# moonclock.net
KiCad netlist of a schematic drawn in EAGLE
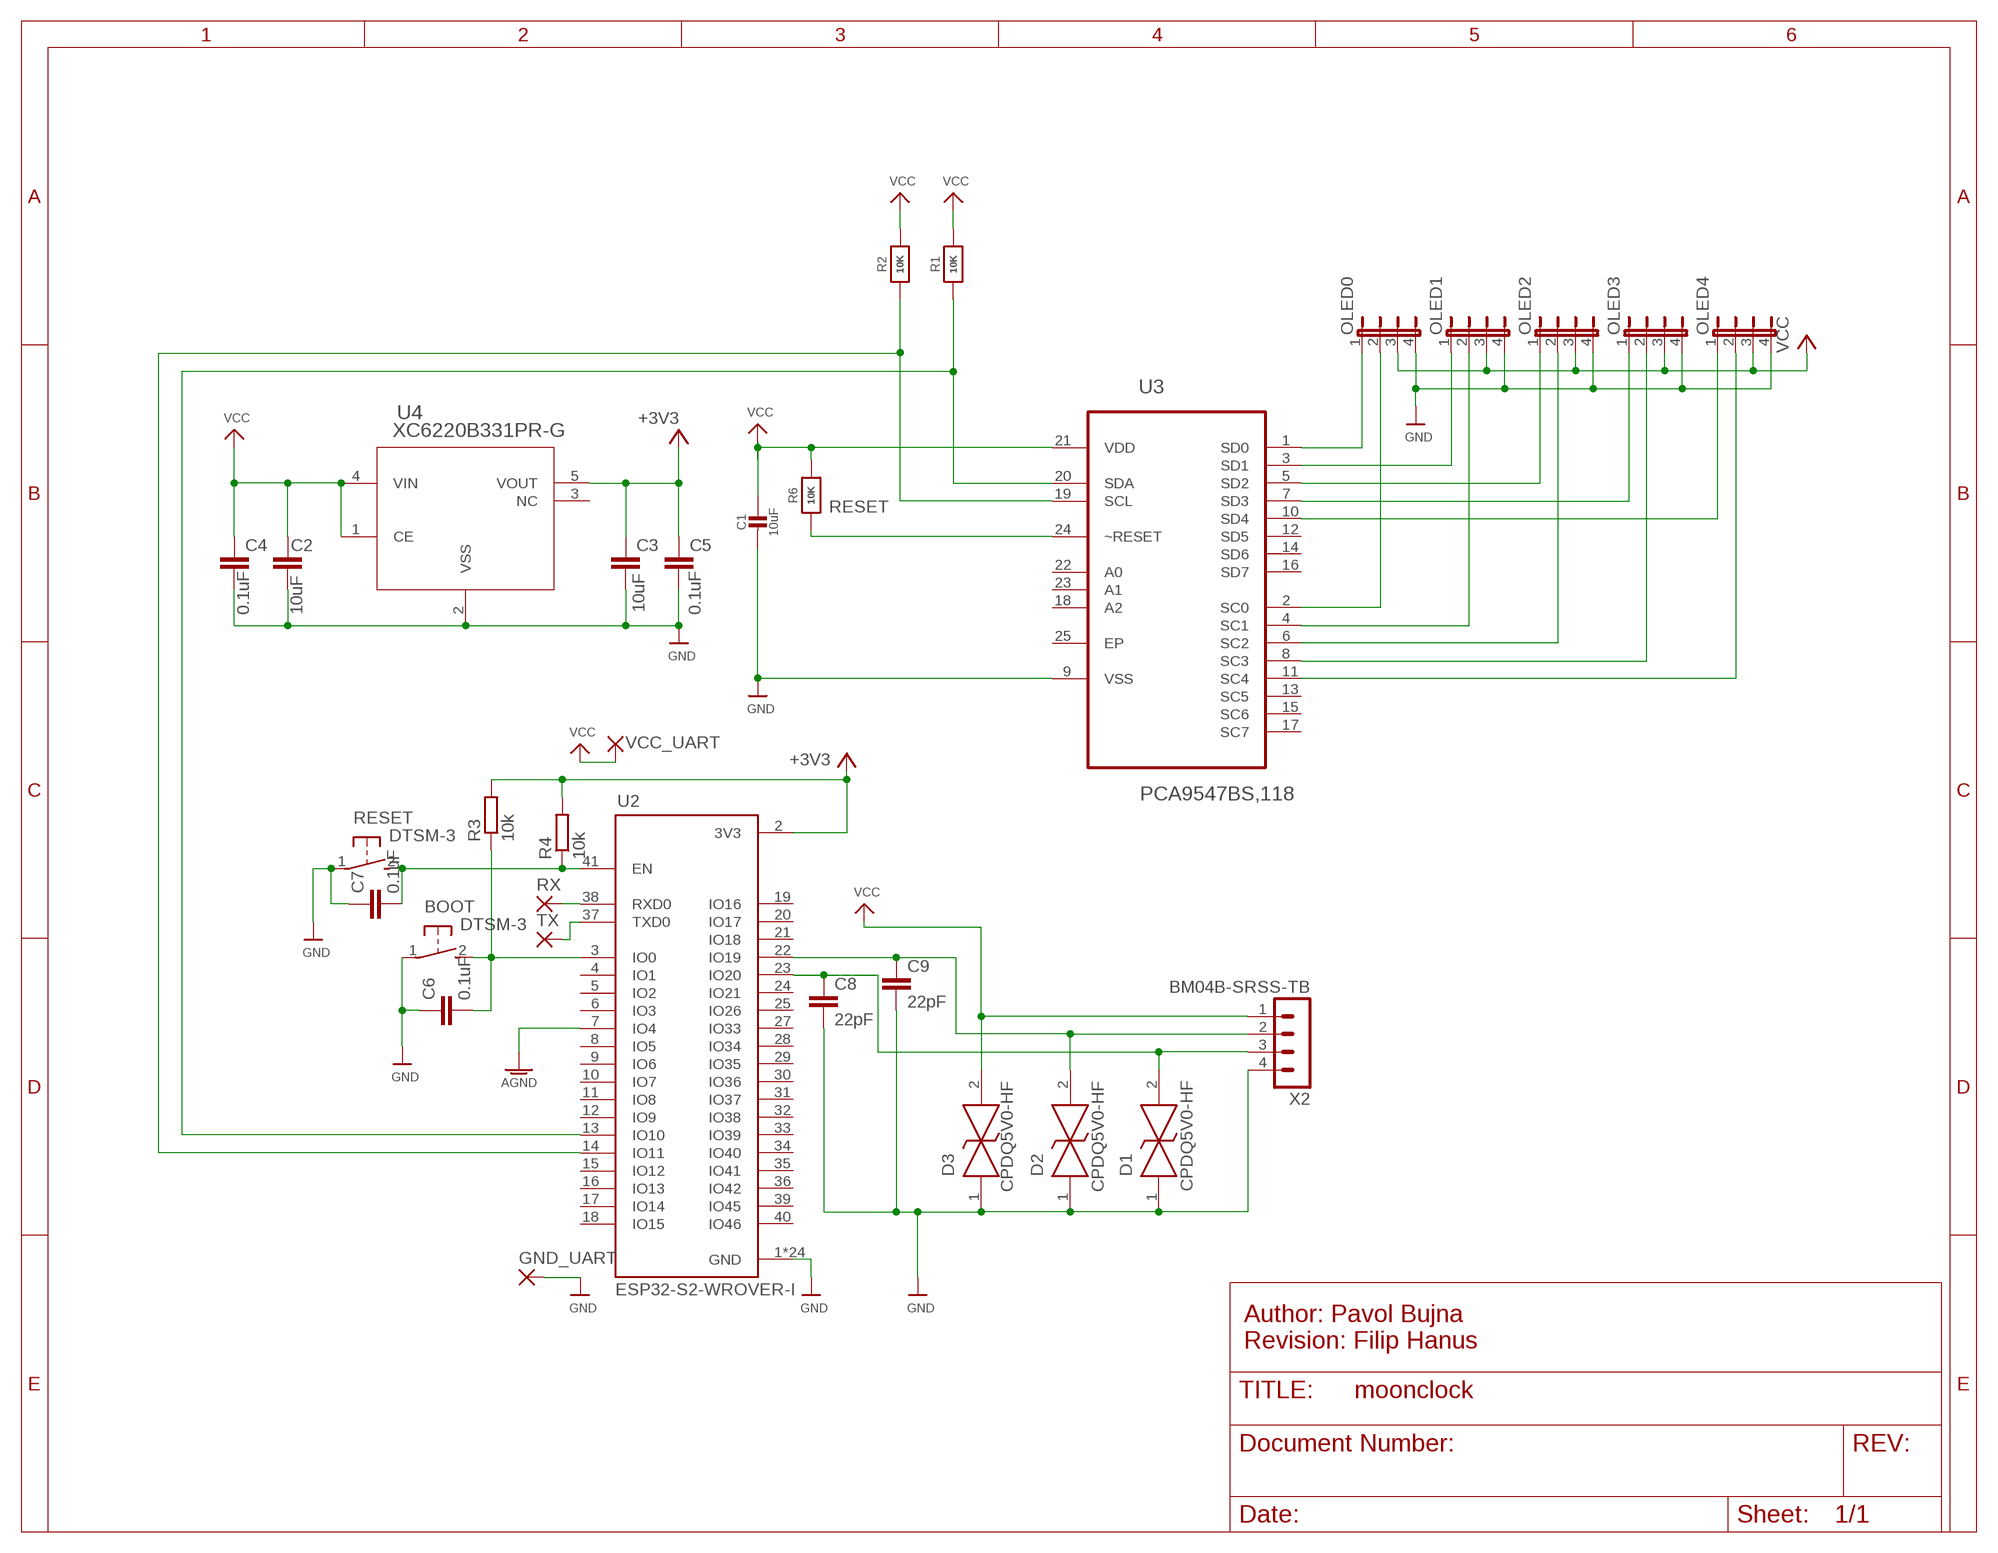
[diagram p0: schematic, sheet 1]

(export (version "E")
  (design (tool "Eeschema 10.0.6"))
  (components
    (comp (ref "BOOT")
      (value "DTSM-3")
      (footprint "eagle-import:DTSM-3")
      (libsource (lib "eagle-import") (part "DTSM-3"))
    )
    (comp (ref "C1")
      (value "10uF")
      (footprint "eagle-import:0805-NO")
      (libsource (lib "eagle-import") (part "CAP_CERAMIC0805-NOOUTLINE"))
    )
    (comp (ref "C2")
      (value "10uF")
      (footprint "eagle-import:C0805")
      (libsource (lib "eagle-import") (part "C-EUC0805"))
    )
    (comp (ref "C3")
      (value "10uF")
      (footprint "eagle-import:C0805")
      (libsource (lib "eagle-import") (part "C-EUC0805"))
    )
    (comp (ref "C4")
      (value "0.1uF")
      (footprint "eagle-import:C0805")
      (libsource (lib "eagle-import") (part "C-EUC0805"))
    )
    (comp (ref "C5")
      (value "0.1uF")
      (footprint "eagle-import:C0805")
      (libsource (lib "eagle-import") (part "C-EUC0805"))
    )
    (comp (ref "C6")
      (value "0.1uF")
      (footprint "eagle-import:C0805")
      (libsource (lib "eagle-import") (part "C-EUC0805"))
    )
    (comp (ref "C7")
      (value "0.1uF")
      (footprint "eagle-import:C0805")
      (libsource (lib "eagle-import") (part "C-EUC0805"))
    )
    (comp (ref "C8")
      (value "22pF")
      (footprint "eagle-import:C0805")
      (libsource (lib "eagle-import") (part "C-EUC0805"))
    )
    (comp (ref "C9")
      (value "22pF")
      (footprint "eagle-import:C0805")
      (libsource (lib "eagle-import") (part "C-EUC0805"))
    )
    (comp (ref "D1")
      (value "CPDQ5V0-HF")
      (footprint "eagle-import:MBTB-D-SOD-923F-IMP-0402")
      (fields (field (name "MF") "Comchip Technology"))
      (libsource (lib "eagle-import") (part "CPDQ5V0-HF"))
    )
    (comp (ref "D2")
      (value "CPDQ5V0-HF")
      (footprint "eagle-import:MBTB-D-SOD-923F-IMP-0402")
      (fields (field (name "MF") "Comchip Technology"))
      (libsource (lib "eagle-import") (part "CPDQ5V0-HF"))
    )
    (comp (ref "D3")
      (value "CPDQ5V0-HF")
      (footprint "eagle-import:MBTB-D-SOD-923F-IMP-0402")
      (fields (field (name "MF") "Comchip Technology"))
      (libsource (lib "eagle-import") (part "CPDQ5V0-HF"))
    )
    (comp (ref "GND_UART")
      (value "SMD2")
      (footprint "eagle-import:SMD1,27-2,54")
      (libsource (lib "eagle-import") (part "SMD2"))
    )
    (comp (ref "OLED0")
      (value "JP4E")
      (footprint "eagle-import:JP4")
      (libsource (lib "eagle-import") (part "JP4E"))
    )
    (comp (ref "OLED1")
      (value "JP4E")
      (footprint "eagle-import:JP4")
      (libsource (lib "eagle-import") (part "JP4E"))
    )
    (comp (ref "OLED2")
      (value "JP4E")
      (footprint "eagle-import:JP4")
      (libsource (lib "eagle-import") (part "JP4E"))
    )
    (comp (ref "OLED3")
      (value "JP4E")
      (footprint "eagle-import:JP4")
      (libsource (lib "eagle-import") (part "JP4E"))
    )
    (comp (ref "OLED4")
      (value "JP4E")
      (footprint "eagle-import:JP4")
      (libsource (lib "eagle-import") (part "JP4E"))
    )
    (comp (ref "R1")
      (value "10K")
      (footprint "eagle-import:0805-NO")
      (libsource (lib "eagle-import") (part "RESISTOR0805_NOOUTLINE"))
    )
    (comp (ref "R2")
      (value "10K")
      (footprint "eagle-import:0805-NO")
      (libsource (lib "eagle-import") (part "RESISTOR0805_NOOUTLINE"))
    )
    (comp (ref "R3")
      (value "10k")
      (footprint "eagle-import:R0805")
      (libsource (lib "eagle-import") (part "R-EU_R0805"))
    )
    (comp (ref "R4")
      (value "10k")
      (footprint "eagle-import:R0805")
      (libsource (lib "eagle-import") (part "R-EU_R0805"))
    )
    (comp (ref "R6")
      (value "10K")
      (footprint "eagle-import:_0805MP")
      (libsource (lib "eagle-import") (part "RESISTOR_0805MP"))
    )
    (comp (ref "RESET")
      (value "DTSM-3")
      (footprint "eagle-import:DTSM-3")
      (libsource (lib "eagle-import") (part "DTSM-3"))
    )
    (comp (ref "RX")
      (value "SMD2")
      (footprint "eagle-import:SMD1,27-2,54")
      (libsource (lib "eagle-import") (part "SMD2"))
    )
    (comp (ref "TX")
      (value "SMD2")
      (footprint "eagle-import:SMD1,27-2,54")
      (libsource (lib "eagle-import") (part "SMD2"))
    )
    (comp (ref "U2")
      (value "ESP32-S2-WROVER-I")
      (footprint "eagle-import:ESP32-S2-WROVER-I")
      (libsource (lib "eagle-import") (part "ESP32-S2-WROVER-I"))
    )
    (comp (ref "U3")
      (value "PCA9547BS,118")
      (footprint "eagle-import:QFN50P400X400X100-25N")
      (fields (field (name "MF") "NXP Semiconductors"))
      (libsource (lib "eagle-import") (part "PCA9547BS,118"))
    )
    (comp (ref "U4")
      (value "XC6220B331PR-G")
      (footprint "eagle-import:SOT-89-5_TOR")
      (fields (field (name "COPYRIGHT") "Copyright (C) 2022 Ultra Librarian. All rights reserved."))
      (libsource (lib "eagle-import") (part "XC6220B331PR-G"))
    )
    (comp (ref "VCC_UART")
      (value "SMD2")
      (footprint "eagle-import:SMD1,27-2,54")
      (libsource (lib "eagle-import") (part "SMD2"))
    )
    (comp (ref "X2")
      (value "BM04B-SRSS-TB")
      (footprint "eagle-import:BM04B-SRSS-TB")
      (libsource (lib "eagle-import") (part "BM04B-SRSS-TB"))
    )
  )
  (nets
    (net (code "1") (name "+3V3") (class "Default")
      (node (ref "C3") (pin "1") (pinfunction "1_1") (pintype "passive"))
      (node (ref "C5") (pin "1") (pinfunction "1_1") (pintype "passive"))
      (node (ref "R3") (pin "2") (pinfunction "2_2") (pintype "passive"))
      (node (ref "R4") (pin "2") (pinfunction "2_2") (pintype "passive"))
      (node (ref "U4") (pin "5") (pinfunction "VOUT_5") (pintype "output"))
    )
    (net (code "2") (name "/RESET") (class "Default")
      (node (ref "R6") (pin "1") (pinfunction "1_1") (pintype "passive"))
      (node (ref "U3") (pin "24") (pinfunction "~{RESET}_24") (pintype "input"))
    )
    (net (code "3") (name "AGND") (class "Default")
      (node (ref "U2") (pin "7") (pinfunction "IO4_7") (pintype "bidirectional"))
    )
    (net (code "4") (name "GND") (class "Default")
      (node (ref "BOOT") (pin "1") (pinfunction "1_1") (pintype "passive"))
      (node (ref "C1") (pin "2") (pinfunction "2_2") (pintype "passive"))
      (node (ref "C2") (pin "2") (pinfunction "2_2") (pintype "passive"))
      (node (ref "C3") (pin "2") (pinfunction "2_2") (pintype "passive"))
      (node (ref "C4") (pin "2") (pinfunction "2_2") (pintype "passive"))
      (node (ref "C5") (pin "2") (pinfunction "2_2") (pintype "passive"))
      (node (ref "C6") (pin "1") (pinfunction "1_1") (pintype "passive"))
      (node (ref "C7") (pin "1") (pinfunction "1_1") (pintype "passive"))
      (node (ref "C8") (pin "2") (pinfunction "2_2") (pintype "passive"))
      (node (ref "C9") (pin "2") (pinfunction "2_2") (pintype "passive"))
      (node (ref "D1") (pin "1") (pinfunction "K_1") (pintype "bidirectional"))
      (node (ref "D2") (pin "1") (pinfunction "K_1") (pintype "bidirectional"))
      (node (ref "D3") (pin "1") (pinfunction "K_1") (pintype "bidirectional"))
      (node (ref "GND_UART") (pin "1") (pinfunction "P_1") (pintype "passive"))
      (node (ref "OLED0") (pin "4") (pinfunction "4_4") (pintype "passive"))
      (node (ref "OLED1") (pin "4") (pinfunction "4_4") (pintype "passive"))
      (node (ref "OLED2") (pin "4") (pinfunction "4_4") (pintype "passive"))
      (node (ref "OLED3") (pin "4") (pinfunction "4_4") (pintype "passive"))
      (node (ref "OLED4") (pin "4") (pinfunction "4_4") (pintype "passive"))
      (node (ref "RESET") (pin "1") (pinfunction "1_1") (pintype "passive"))
      (node (ref "U2") (pin "1") (pinfunction "GND_1") (pintype "power_in"))
      (node (ref "U2") (pin "26") (pinfunction "GND_26") (pintype "power_in"))
      (node (ref "U2") (pin "42") (pinfunction "GND_42") (pintype "power_in"))
      (node (ref "U2") (pin "43.1") (pinfunction "GND_43.1") (pintype "power_in"))
      (node (ref "U2") (pin "43.10") (pinfunction "GND_43.10") (pintype "power_in"))
      (node (ref "U2") (pin "43.11") (pinfunction "GND_43.11") (pintype "power_in"))
      (node (ref "U2") (pin "43.12") (pinfunction "GND_43.12") (pintype "power_in"))
      (node (ref "U2") (pin "43.13") (pinfunction "GND_43.13") (pintype "power_in"))
      (node (ref "U2") (pin "43.14") (pinfunction "GND_43.14") (pintype "power_in"))
      (node (ref "U2") (pin "43.15") (pinfunction "GND_43.15") (pintype "power_in"))
      (node (ref "U2") (pin "43.16") (pinfunction "GND_43.16") (pintype "power_in"))
      (node (ref "U2") (pin "43.17") (pinfunction "GND_43.17") (pintype "power_in"))
      (node (ref "U2") (pin "43.18") (pinfunction "GND_43.18") (pintype "power_in"))
      (node (ref "U2") (pin "43.19") (pinfunction "GND_43.19") (pintype "power_in"))
      (node (ref "U2") (pin "43.2") (pinfunction "GND_43.2") (pintype "power_in"))
      (node (ref "U2") (pin "43.20") (pinfunction "GND_43.20") (pintype "power_in"))
      (node (ref "U2") (pin "43.21") (pinfunction "GND_43.21") (pintype "power_in"))
      (node (ref "U2") (pin "43.3") (pinfunction "GND_43.3") (pintype "power_in"))
      (node (ref "U2") (pin "43.4") (pinfunction "GND_43.4") (pintype "power_in"))
      (node (ref "U2") (pin "43.5") (pinfunction "GND_43.5") (pintype "power_in"))
      (node (ref "U2") (pin "43.6") (pinfunction "GND_43.6") (pintype "power_in"))
      (node (ref "U2") (pin "43.7") (pinfunction "GND_43.7") (pintype "power_in"))
      (node (ref "U2") (pin "43.8") (pinfunction "GND_43.8") (pintype "power_in"))
      (node (ref "U2") (pin "43.9") (pinfunction "GND_43.9") (pintype "power_in"))
      (node (ref "U3") (pin "9") (pinfunction "VSS_9") (pintype "passive"))
      (node (ref "U4") (pin "2") (pinfunction "VSS_2") (pintype "passive"))
      (node (ref "X2") (pin "4") (pinfunction "4_4") (pintype "passive"))
    )
    (net (code "5") (name "Net-(D1-A)") (class "Default")
      (node (ref "C8") (pin "1") (pinfunction "1_1") (pintype "passive"))
      (node (ref "D1") (pin "2") (pinfunction "A_2") (pintype "bidirectional"))
      (node (ref "U2") (pin "23") (pinfunction "IO20_23") (pintype "bidirectional"))
      (node (ref "X2") (pin "3") (pinfunction "3_3") (pintype "passive"))
    )
    (net (code "6") (name "Net-(D2-A)") (class "Default")
      (node (ref "C9") (pin "1") (pinfunction "1_1") (pintype "passive"))
      (node (ref "D2") (pin "2") (pinfunction "A_2") (pintype "bidirectional"))
      (node (ref "U2") (pin "22") (pinfunction "IO19_22") (pintype "bidirectional"))
      (node (ref "X2") (pin "2") (pinfunction "2_2") (pintype "passive"))
    )
    (net (code "7") (name "Net-(RX-P)") (class "Default")
      (node (ref "RX") (pin "1") (pinfunction "P_1") (pintype "passive"))
      (node (ref "U2") (pin "38") (pinfunction "RXD0_38") (pintype "bidirectional"))
    )
    (net (code "8") (name "Net-(TX-P)") (class "Default")
      (node (ref "TX") (pin "1") (pinfunction "P_1") (pintype "passive"))
      (node (ref "U2") (pin "37") (pinfunction "TXD0_37") (pintype "bidirectional"))
    )
    (net (code "9") (name "Net-(U2-EN)") (class "Default")
      (node (ref "C7") (pin "2") (pinfunction "2_2") (pintype "passive"))
      (node (ref "R4") (pin "1") (pinfunction "1_1") (pintype "passive"))
      (node (ref "RESET") (pin "2") (pinfunction "2_2") (pintype "passive"))
      (node (ref "U2") (pin "41") (pinfunction "EN_41") (pintype "input"))
    )
    (net (code "10") (name "Net-(U2-IO0)") (class "Default")
      (node (ref "BOOT") (pin "2") (pinfunction "2_2") (pintype "passive"))
      (node (ref "C6") (pin "2") (pinfunction "2_2") (pintype "passive"))
      (node (ref "R3") (pin "1") (pinfunction "1_1") (pintype "passive"))
      (node (ref "U2") (pin "3") (pinfunction "IO0_3") (pintype "bidirectional"))
    )
    (net (code "11") (name "Net-(U2-IO10)") (class "Default")
      (node (ref "R1") (pin "1") (pinfunction "1_1") (pintype "passive"))
      (node (ref "U2") (pin "13") (pinfunction "IO10_13") (pintype "bidirectional"))
      (node (ref "U3") (pin "20") (pinfunction "SDA_20") (pintype "bidirectional"))
    )
    (net (code "12") (name "Net-(U2-IO11)") (class "Default")
      (node (ref "R2") (pin "1") (pinfunction "1_1") (pintype "passive"))
      (node (ref "U2") (pin "14") (pinfunction "IO11_14") (pintype "bidirectional"))
      (node (ref "U3") (pin "19") (pinfunction "SCL_19") (pintype "input"))
    )
    (net (code "13") (name "Net-(U3-SC0)") (class "Default")
      (node (ref "OLED0") (pin "2") (pinfunction "2_2") (pintype "passive"))
      (node (ref "U3") (pin "2") (pinfunction "SC0_2") (pintype "output"))
    )
    (net (code "14") (name "Net-(U3-SC1)") (class "Default")
      (node (ref "OLED1") (pin "2") (pinfunction "2_2") (pintype "passive"))
      (node (ref "U3") (pin "4") (pinfunction "SC1_4") (pintype "output"))
    )
    (net (code "15") (name "Net-(U3-SC2)") (class "Default")
      (node (ref "OLED2") (pin "2") (pinfunction "2_2") (pintype "passive"))
      (node (ref "U3") (pin "6") (pinfunction "SC2_6") (pintype "output"))
    )
    (net (code "16") (name "Net-(U3-SC3)") (class "Default")
      (node (ref "OLED3") (pin "2") (pinfunction "2_2") (pintype "passive"))
      (node (ref "U3") (pin "8") (pinfunction "SC3_8") (pintype "output"))
    )
    (net (code "17") (name "Net-(U3-SC4)") (class "Default")
      (node (ref "OLED4") (pin "2") (pinfunction "2_2") (pintype "passive"))
      (node (ref "U3") (pin "11") (pinfunction "SC4_11") (pintype "output"))
    )
    (net (code "18") (name "Net-(U3-SD0)") (class "Default")
      (node (ref "OLED0") (pin "1") (pinfunction "1_1") (pintype "passive"))
      (node (ref "U3") (pin "1") (pinfunction "SD0_1") (pintype "output"))
    )
    (net (code "19") (name "Net-(U3-SD1)") (class "Default")
      (node (ref "OLED1") (pin "1") (pinfunction "1_1") (pintype "passive"))
      (node (ref "U3") (pin "3") (pinfunction "SD1_3") (pintype "output"))
    )
    (net (code "20") (name "Net-(U3-SD2)") (class "Default")
      (node (ref "OLED2") (pin "1") (pinfunction "1_1") (pintype "passive"))
      (node (ref "U3") (pin "5") (pinfunction "SD2_5") (pintype "output"))
    )
    (net (code "21") (name "Net-(U3-SD3)") (class "Default")
      (node (ref "OLED3") (pin "1") (pinfunction "1_1") (pintype "passive"))
      (node (ref "U3") (pin "7") (pinfunction "SD3_7") (pintype "output"))
    )
    (net (code "22") (name "Net-(U3-SD4)") (class "Default")
      (node (ref "OLED4") (pin "1") (pinfunction "1_1") (pintype "passive"))
      (node (ref "U3") (pin "10") (pinfunction "SD4_10") (pintype "output"))
    )
    (net (code "23") (name "VCC") (class "Default")
      (node (ref "C1") (pin "1") (pinfunction "1_1") (pintype "passive"))
      (node (ref "C2") (pin "1") (pinfunction "1_1") (pintype "passive"))
      (node (ref "C4") (pin "1") (pinfunction "1_1") (pintype "passive"))
      (node (ref "D3") (pin "2") (pinfunction "A_2") (pintype "bidirectional"))
      (node (ref "OLED0") (pin "3") (pinfunction "3_3") (pintype "passive"))
      (node (ref "OLED1") (pin "3") (pinfunction "3_3") (pintype "passive"))
      (node (ref "OLED2") (pin "3") (pinfunction "3_3") (pintype "passive"))
      (node (ref "OLED3") (pin "3") (pinfunction "3_3") (pintype "passive"))
      (node (ref "OLED4") (pin "3") (pinfunction "3_3") (pintype "passive"))
      (node (ref "R1") (pin "2") (pinfunction "2_2") (pintype "passive"))
      (node (ref "R2") (pin "2") (pinfunction "2_2") (pintype "passive"))
      (node (ref "R6") (pin "2") (pinfunction "2_2") (pintype "passive"))
      (node (ref "U3") (pin "21") (pinfunction "VDD_21") (pintype "power_in"))
      (node (ref "U4") (pin "1") (pinfunction "CE_1") (pintype "passive"))
      (node (ref "U4") (pin "4") (pinfunction "VIN_4") (pintype "power_in"))
      (node (ref "VCC_UART") (pin "1") (pinfunction "P_1") (pintype "passive"))
      (node (ref "X2") (pin "1") (pinfunction "1_1") (pintype "passive"))
    )
    (net (code "24") (name "unconnected-(U2-3V3-Pad2)") (class "Default")
      (node (ref "U2") (pin "2") (pinfunction "3V3_2") (pintype "power_in"))
    )
    (net (code "25") (name "unconnected-(U2-IO1-Pad4)") (class "Default")
      (node (ref "U2") (pin "4") (pinfunction "IO1_4") (pintype "bidirectional"))
    )
    (net (code "26") (name "unconnected-(U2-IO2-Pad5)") (class "Default")
      (node (ref "U2") (pin "5") (pinfunction "IO2_5") (pintype "bidirectional"))
    )
    (net (code "27") (name "unconnected-(U2-IO3-Pad6)") (class "Default")
      (node (ref "U2") (pin "6") (pinfunction "IO3_6") (pintype "bidirectional"))
    )
    (net (code "28") (name "unconnected-(U2-IO5-Pad8)") (class "Default")
      (node (ref "U2") (pin "8") (pinfunction "IO5_8") (pintype "bidirectional"))
    )
    (net (code "29") (name "unconnected-(U2-IO6-Pad9)") (class "Default")
      (node (ref "U2") (pin "9") (pinfunction "IO6_9") (pintype "bidirectional"))
    )
    (net (code "30") (name "unconnected-(U2-IO7-Pad10)") (class "Default")
      (node (ref "U2") (pin "10") (pinfunction "IO7_10") (pintype "bidirectional"))
    )
    (net (code "31") (name "unconnected-(U2-IO8-Pad11)") (class "Default")
      (node (ref "U2") (pin "11") (pinfunction "IO8_11") (pintype "bidirectional"))
    )
    (net (code "32") (name "unconnected-(U2-IO9-Pad12)") (class "Default")
      (node (ref "U2") (pin "12") (pinfunction "IO9_12") (pintype "bidirectional"))
    )
    (net (code "33") (name "unconnected-(U2-IO12-Pad15)") (class "Default")
      (node (ref "U2") (pin "15") (pinfunction "IO12_15") (pintype "bidirectional"))
    )
    (net (code "34") (name "unconnected-(U2-IO13-Pad16)") (class "Default")
      (node (ref "U2") (pin "16") (pinfunction "IO13_16") (pintype "bidirectional"))
    )
    (net (code "35") (name "unconnected-(U2-IO14-Pad17)") (class "Default")
      (node (ref "U2") (pin "17") (pinfunction "IO14_17") (pintype "bidirectional"))
    )
    (net (code "36") (name "unconnected-(U2-IO15-Pad18)") (class "Default")
      (node (ref "U2") (pin "18") (pinfunction "IO15_18") (pintype "bidirectional"))
    )
    (net (code "37") (name "unconnected-(U2-IO16-Pad19)") (class "Default")
      (node (ref "U2") (pin "19") (pinfunction "IO16_19") (pintype "bidirectional"))
    )
    (net (code "38") (name "unconnected-(U2-IO17-Pad20)") (class "Default")
      (node (ref "U2") (pin "20") (pinfunction "IO17_20") (pintype "bidirectional"))
    )
    (net (code "39") (name "unconnected-(U2-IO18-Pad21)") (class "Default")
      (node (ref "U2") (pin "21") (pinfunction "IO18_21") (pintype "bidirectional"))
    )
    (net (code "40") (name "unconnected-(U2-IO21-Pad24)") (class "Default")
      (node (ref "U2") (pin "24") (pinfunction "IO21_24") (pintype "bidirectional"))
    )
    (net (code "41") (name "unconnected-(U2-IO26-Pad25)") (class "Default")
      (node (ref "U2") (pin "25") (pinfunction "IO26_25") (pintype "bidirectional"))
    )
    (net (code "42") (name "unconnected-(U2-IO33-Pad27)") (class "Default")
      (node (ref "U2") (pin "27") (pinfunction "IO33_27") (pintype "bidirectional"))
    )
    (net (code "43") (name "unconnected-(U2-IO34-Pad28)") (class "Default")
      (node (ref "U2") (pin "28") (pinfunction "IO34_28") (pintype "bidirectional"))
    )
    (net (code "44") (name "unconnected-(U2-IO35-Pad29)") (class "Default")
      (node (ref "U2") (pin "29") (pinfunction "IO35_29") (pintype "bidirectional"))
    )
    (net (code "45") (name "unconnected-(U2-IO36-Pad30)") (class "Default")
      (node (ref "U2") (pin "30") (pinfunction "IO36_30") (pintype "bidirectional"))
    )
    (net (code "46") (name "unconnected-(U2-IO37-Pad31)") (class "Default")
      (node (ref "U2") (pin "31") (pinfunction "IO37_31") (pintype "bidirectional"))
    )
    (net (code "47") (name "unconnected-(U2-IO38-Pad32)") (class "Default")
      (node (ref "U2") (pin "32") (pinfunction "IO38_32") (pintype "bidirectional"))
    )
    (net (code "48") (name "unconnected-(U2-IO39-Pad33)") (class "Default")
      (node (ref "U2") (pin "33") (pinfunction "IO39_33") (pintype "bidirectional"))
    )
    (net (code "49") (name "unconnected-(U2-IO40-Pad34)") (class "Default")
      (node (ref "U2") (pin "34") (pinfunction "IO40_34") (pintype "bidirectional"))
    )
    (net (code "50") (name "unconnected-(U2-IO41-Pad35)") (class "Default")
      (node (ref "U2") (pin "35") (pinfunction "IO41_35") (pintype "bidirectional"))
    )
    (net (code "51") (name "unconnected-(U2-IO42-Pad36)") (class "Default")
      (node (ref "U2") (pin "36") (pinfunction "IO42_36") (pintype "bidirectional"))
    )
    (net (code "52") (name "unconnected-(U2-IO45-Pad39)") (class "Default")
      (node (ref "U2") (pin "39") (pinfunction "IO45_39") (pintype "bidirectional"))
    )
    (net (code "53") (name "unconnected-(U2-IO46-Pad40)") (class "Default")
      (node (ref "U2") (pin "40") (pinfunction "IO46_40") (pintype "bidirectional"))
    )
    (net (code "54") (name "unconnected-(U3-A0-Pad22)") (class "Default")
      (node (ref "U3") (pin "22") (pinfunction "A0_22") (pintype "input"))
    )
    (net (code "55") (name "unconnected-(U3-A1-Pad23)") (class "Default")
      (node (ref "U3") (pin "23") (pinfunction "A1_23") (pintype "input"))
    )
    (net (code "56") (name "unconnected-(U3-A2-Pad18)") (class "Default")
      (node (ref "U3") (pin "18") (pinfunction "A2_18") (pintype "input"))
    )
    (net (code "57") (name "unconnected-(U3-EP-Pad25)") (class "Default")
      (node (ref "U3") (pin "25") (pinfunction "EP_25") (pintype "passive"))
    )
    (net (code "58") (name "unconnected-(U3-SC5-Pad13)") (class "Default")
      (node (ref "U3") (pin "13") (pinfunction "SC5_13") (pintype "output"))
    )
    (net (code "59") (name "unconnected-(U3-SC6-Pad15)") (class "Default")
      (node (ref "U3") (pin "15") (pinfunction "SC6_15") (pintype "output"))
    )
    (net (code "60") (name "unconnected-(U3-SC7-Pad17)") (class "Default")
      (node (ref "U3") (pin "17") (pinfunction "SC7_17") (pintype "output"))
    )
    (net (code "61") (name "unconnected-(U3-SD5-Pad12)") (class "Default")
      (node (ref "U3") (pin "12") (pinfunction "SD5_12") (pintype "output"))
    )
    (net (code "62") (name "unconnected-(U3-SD6-Pad14)") (class "Default")
      (node (ref "U3") (pin "14") (pinfunction "SD6_14") (pintype "output"))
    )
    (net (code "63") (name "unconnected-(U3-SD7-Pad16)") (class "Default")
      (node (ref "U3") (pin "16") (pinfunction "SD7_16") (pintype "output"))
    )
    (net (code "64") (name "unconnected-(U4-NC-Pad3)") (class "Default")
      (node (ref "U4") (pin "3") (pinfunction "NC_3") (pintype "no_connect"))
    )
  )
)
